# BLE_--_HM-10_--_Breakout_v1_0.net
KiCad netlist of a schematic drawn in EAGLE
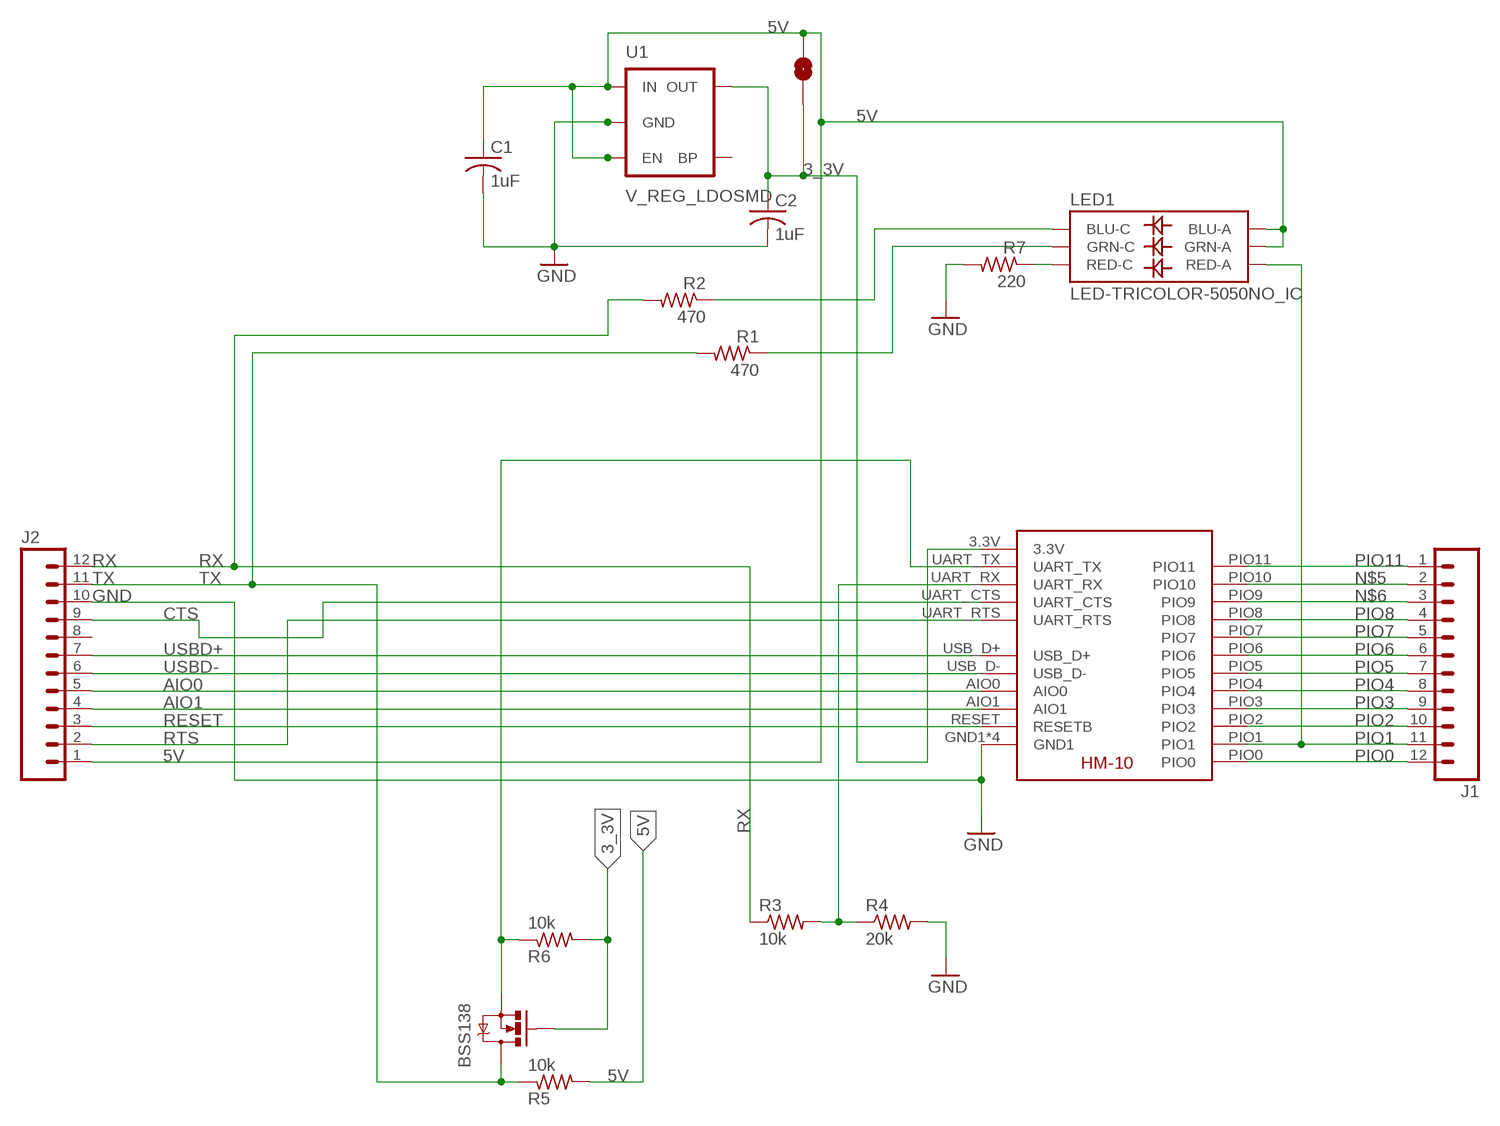
[diagram p0: schematic, sheet 1]

(export (version "E")
  (design (tool "Eeschema 10.0.6"))
  (components
    (comp (ref "BSS138")
      (value "MOSFET-NCHANNELSMD")
      (footprint "eagle-import:SOT23-3")
      (libsource (lib "eagle-import") (part "MOSFET-NCHANNELSMD"))
    )
    (comp (ref "C1")
      (value "1uF")
      (footprint "eagle-import:C0805K")
      (libsource (lib "eagle-import") (part "C-USC0805K"))
    )
    (comp (ref "C2")
      (value "1uF")
      (footprint "eagle-import:C0805K")
      (libsource (lib "eagle-import") (part "C-USC0805K"))
    )
    (comp (ref "J1")
      (value "M12LOCK")
      (footprint "eagle-import:1X12_LOCK")
      (libsource (lib "eagle-import") (part "M12LOCK"))
    )
    (comp (ref "J2")
      (value "M12LOCK")
      (footprint "eagle-import:1X12_LOCK")
      (libsource (lib "eagle-import") (part "M12LOCK"))
    )
    (comp (ref "LED1")
      (value "LED-TRICOLOR-5050NO_IC")
      (footprint "eagle-import:LED-TRICOLOR-5050")
      (libsource (lib "eagle-import") (part "LED-TRICOLOR-5050NO_IC"))
    )
    (comp (ref "R1")
      (value "470")
      (footprint "eagle-import:M0805")
      (libsource (lib "eagle-import") (part "R-US_M0805"))
    )
    (comp (ref "R2")
      (value "470")
      (footprint "eagle-import:M0805")
      (libsource (lib "eagle-import") (part "R-US_M0805"))
    )
    (comp (ref "R3")
      (value "10k")
      (footprint "eagle-import:M0805")
      (libsource (lib "eagle-import") (part "R-US_M0805"))
    )
    (comp (ref "R4")
      (value "20k")
      (footprint "eagle-import:M0805")
      (libsource (lib "eagle-import") (part "R-US_M0805"))
    )
    (comp (ref "R5")
      (value "10k")
      (footprint "eagle-import:M0805")
      (libsource (lib "eagle-import") (part "R-US_M0805"))
    )
    (comp (ref "R6")
      (value "10k")
      (footprint "eagle-import:M0805")
      (libsource (lib "eagle-import") (part "R-US_M0805"))
    )
    (comp (ref "R7")
      (value "220")
      (footprint "eagle-import:M0805")
      (libsource (lib "eagle-import") (part "R-US_M0805"))
    )
    (comp (ref "SJ1")
      (value "SOLDERJUMPERNO")
      (footprint "eagle-import:SJ_2S-NO")
      (libsource (lib "eagle-import") (part "SOLDERJUMPERNO"))
    )
    (comp (ref "U$1")
      (value "BLE-HM-10")
      (footprint "eagle-import:BLE-HM-10")
      (libsource (lib "eagle-import") (part "BLE-HM-10"))
    )
    (comp (ref "U1")
      (value "V_REG_LDOSMD")
      (footprint "eagle-import:SOT23-5")
      (libsource (lib "eagle-import") (part "V_REG_LDOSMD"))
    )
  )
  (nets
    (net (code "1") (name "/AIO0") (class "Default")
      (node (ref "J2") (pin "5") (pinfunction "5_5") (pintype "passive"))
      (node (ref "U$1") (pin "AIO0") (pinfunction "AIO0_AIO0") (pintype "bidirectional"))
    )
    (net (code "2") (name "/AIO1") (class "Default")
      (node (ref "J2") (pin "4") (pinfunction "4_4") (pintype "passive"))
      (node (ref "U$1") (pin "AIO1") (pinfunction "AIO1_AIO1") (pintype "bidirectional"))
    )
    (net (code "3") (name "/CTS") (class "Default")
      (node (ref "J2") (pin "9") (pinfunction "9_9") (pintype "passive"))
      (node (ref "U$1") (pin "UART_CTS") (pinfunction "UART_CTS_UART_CTS") (pintype "bidirectional"))
    )
    (net (code "4") (name "/N$5") (class "Default")
      (node (ref "J1") (pin "2") (pinfunction "2_2") (pintype "passive"))
      (node (ref "U$1") (pin "PIO10") (pinfunction "PIO10_PIO10") (pintype "bidirectional"))
    )
    (net (code "5") (name "/N$6") (class "Default")
      (node (ref "J1") (pin "3") (pinfunction "3_3") (pintype "passive"))
      (node (ref "U$1") (pin "PIO9") (pinfunction "PIO9_PIO9") (pintype "bidirectional"))
    )
    (net (code "6") (name "/PIO0") (class "Default")
      (node (ref "J1") (pin "12") (pinfunction "12_12") (pintype "passive"))
      (node (ref "U$1") (pin "PIO0") (pinfunction "PIO0_PIO0") (pintype "bidirectional"))
    )
    (net (code "7") (name "/PIO1") (class "Default")
      (node (ref "J1") (pin "11") (pinfunction "11_11") (pintype "passive"))
      (node (ref "LED1") (pin "2") (pinfunction "RED-A_2") (pintype "bidirectional"))
      (node (ref "U$1") (pin "PIO1") (pinfunction "PIO1_PIO1") (pintype "bidirectional"))
    )
    (net (code "8") (name "/PIO2") (class "Default")
      (node (ref "J1") (pin "10") (pinfunction "10_10") (pintype "passive"))
      (node (ref "U$1") (pin "PIO2") (pinfunction "PIO2_PIO2") (pintype "bidirectional"))
    )
    (net (code "9") (name "/PIO3") (class "Default")
      (node (ref "J1") (pin "9") (pinfunction "9_9") (pintype "passive"))
      (node (ref "U$1") (pin "PIO3") (pinfunction "PIO3_PIO3") (pintype "bidirectional"))
    )
    (net (code "10") (name "/PIO4") (class "Default")
      (node (ref "J1") (pin "8") (pinfunction "8_8") (pintype "passive"))
      (node (ref "U$1") (pin "PIO4") (pinfunction "PIO4_PIO4") (pintype "bidirectional"))
    )
    (net (code "11") (name "/PIO5") (class "Default")
      (node (ref "J1") (pin "7") (pinfunction "7_7") (pintype "passive"))
      (node (ref "U$1") (pin "PIO5") (pinfunction "PIO5_PIO5") (pintype "bidirectional"))
    )
    (net (code "12") (name "/PIO6") (class "Default")
      (node (ref "J1") (pin "6") (pinfunction "6_6") (pintype "passive"))
      (node (ref "U$1") (pin "PIO6") (pinfunction "PIO6_PIO6") (pintype "bidirectional"))
    )
    (net (code "13") (name "/PIO7") (class "Default")
      (node (ref "J1") (pin "5") (pinfunction "5_5") (pintype "passive"))
      (node (ref "U$1") (pin "PIO7") (pinfunction "PIO7_PIO7") (pintype "bidirectional"))
    )
    (net (code "14") (name "/PIO8") (class "Default")
      (node (ref "J1") (pin "4") (pinfunction "4_4") (pintype "passive"))
      (node (ref "U$1") (pin "PIO8") (pinfunction "PIO8_PIO8") (pintype "bidirectional"))
    )
    (net (code "15") (name "/PIO11") (class "Default")
      (node (ref "J1") (pin "1") (pinfunction "1_1") (pintype "passive"))
      (node (ref "U$1") (pin "PIO11") (pinfunction "PIO11_PIO11") (pintype "bidirectional"))
    )
    (net (code "16") (name "/RESET") (class "Default")
      (node (ref "J2") (pin "3") (pinfunction "3_3") (pintype "passive"))
      (node (ref "U$1") (pin "RESET") (pinfunction "RESETB_RESET") (pintype "bidirectional"))
    )
    (net (code "17") (name "/RTS") (class "Default")
      (node (ref "J2") (pin "2") (pinfunction "2_2") (pintype "passive"))
      (node (ref "U$1") (pin "UART_RTS") (pinfunction "UART_RTS_UART_RTS") (pintype "bidirectional"))
    )
    (net (code "18") (name "/RX") (class "Default")
      (node (ref "J2") (pin "12") (pinfunction "12_12") (pintype "passive"))
      (node (ref "R2") (pin "2") (pinfunction "2_2") (pintype "passive"))
      (node (ref "R3") (pin "1") (pinfunction "1_1") (pintype "passive"))
    )
    (net (code "19") (name "/TX") (class "Default")
      (node (ref "BSS138") (pin "2") (pinfunction "S_2") (pintype "passive"))
      (node (ref "BSS138") (pin "3") (pinfunction "D_3") (pintype "passive"))
      (node (ref "J2") (pin "11") (pinfunction "11_11") (pintype "passive"))
      (node (ref "R1") (pin "2") (pinfunction "2_2") (pintype "passive"))
      (node (ref "R5") (pin "1") (pinfunction "1_1") (pintype "passive"))
      (node (ref "R6") (pin "1") (pinfunction "1_1") (pintype "passive"))
      (node (ref "U$1") (pin "UART_TX") (pinfunction "UART_TX_UART_TX") (pintype "bidirectional"))
    )
    (net (code "20") (name "/USBD+") (class "Default")
      (node (ref "J2") (pin "7") (pinfunction "7_7") (pintype "passive"))
      (node (ref "U$1") (pin "USB_D+") (pinfunction "USB_D+_USB_D+") (pintype "bidirectional"))
    )
    (net (code "21") (name "/USBD-") (class "Default")
      (node (ref "J2") (pin "6") (pinfunction "6_6") (pintype "passive"))
      (node (ref "U$1") (pin "USB_D-") (pinfunction "USB_D-_USB_D-") (pintype "bidirectional"))
    )
    (net (code "22") (name "3_3V") (class "Default")
      (node (ref "BSS138") (pin "1") (pinfunction "G_1") (pintype "passive"))
      (node (ref "C2") (pin "1") (pinfunction "1_1") (pintype "passive"))
      (node (ref "R6") (pin "2") (pinfunction "2_2") (pintype "passive"))
      (node (ref "SJ1") (pin "1") (pinfunction "1_1") (pintype "passive"))
      (node (ref "U$1") (pin "3.3V") (pinfunction "3.3V_3.3V") (pintype "bidirectional"))
      (node (ref "U1") (pin "5") (pinfunction "OUT_5") (pintype "passive"))
    )
    (net (code "23") (name "5V") (class "Default")
      (node (ref "C1") (pin "1") (pinfunction "1_1") (pintype "passive"))
      (node (ref "J2") (pin "1") (pinfunction "1_1") (pintype "passive"))
      (node (ref "LED1") (pin "1") (pinfunction "GRN-A_1") (pintype "bidirectional"))
      (node (ref "LED1") (pin "3") (pinfunction "BLU-A_3") (pintype "bidirectional"))
      (node (ref "R5") (pin "2") (pinfunction "2_2") (pintype "passive"))
      (node (ref "SJ1") (pin "2") (pinfunction "2_2") (pintype "passive"))
      (node (ref "U1") (pin "1") (pinfunction "IN_1") (pintype "input"))
      (node (ref "U1") (pin "3") (pinfunction "EN_3") (pintype "input"))
    )
    (net (code "24") (name "GND") (class "Default")
      (node (ref "C1") (pin "2") (pinfunction "2_2") (pintype "passive"))
      (node (ref "C2") (pin "2") (pinfunction "2_2") (pintype "passive"))
      (node (ref "J2") (pin "10") (pinfunction "10_10") (pintype "passive"))
      (node (ref "R4") (pin "2") (pinfunction "2_2") (pintype "passive"))
      (node (ref "R7") (pin "2") (pinfunction "2_2") (pintype "passive"))
      (node (ref "U$1") (pin "GND1") (pinfunction "GND1_GND1") (pintype "bidirectional"))
      (node (ref "U$1") (pin "GND2") (pinfunction "GND1_GND2") (pintype "bidirectional"))
      (node (ref "U$1") (pin "GND3") (pinfunction "GND1_GND3") (pintype "bidirectional"))
      (node (ref "U$1") (pin "GND4") (pinfunction "GND1_GND4") (pintype "bidirectional"))
      (node (ref "U1") (pin "2") (pinfunction "GND_2") (pintype "input"))
    )
    (net (code "25") (name "Net-(LED1-BLU-C)") (class "Default")
      (node (ref "LED1") (pin "4") (pinfunction "BLU-C_4") (pintype "bidirectional"))
      (node (ref "R2") (pin "1") (pinfunction "1_1") (pintype "passive"))
    )
    (net (code "26") (name "Net-(LED1-GRN-C)") (class "Default")
      (node (ref "LED1") (pin "6") (pinfunction "GRN-C_6") (pintype "bidirectional"))
      (node (ref "R1") (pin "1") (pinfunction "1_1") (pintype "passive"))
    )
    (net (code "27") (name "Net-(LED1-RED-C)") (class "Default")
      (node (ref "LED1") (pin "5") (pinfunction "RED-C_5") (pintype "bidirectional"))
      (node (ref "R7") (pin "1") (pinfunction "1_1") (pintype "passive"))
    )
    (net (code "28") (name "Net-(R3-Pad2)") (class "Default")
      (node (ref "R3") (pin "2") (pinfunction "2_2") (pintype "passive"))
      (node (ref "R4") (pin "1") (pinfunction "1_1") (pintype "passive"))
      (node (ref "U$1") (pin "UART_RX") (pinfunction "UART_RX_UART_RX") (pintype "bidirectional"))
    )
    (net (code "29") (name "unconnected-(J2-Pad8)") (class "Default")
      (node (ref "J2") (pin "8") (pinfunction "8_8") (pintype "passive"))
    )
    (net (code "30") (name "unconnected-(U1-BP-Pad4)") (class "Default")
      (node (ref "U1") (pin "4") (pinfunction "BP_4") (pintype "input"))
    )
  )
)
